# AEGIS_Junction_Box_driver.net
KiCad netlist of a schematic drawn in Altium Designer
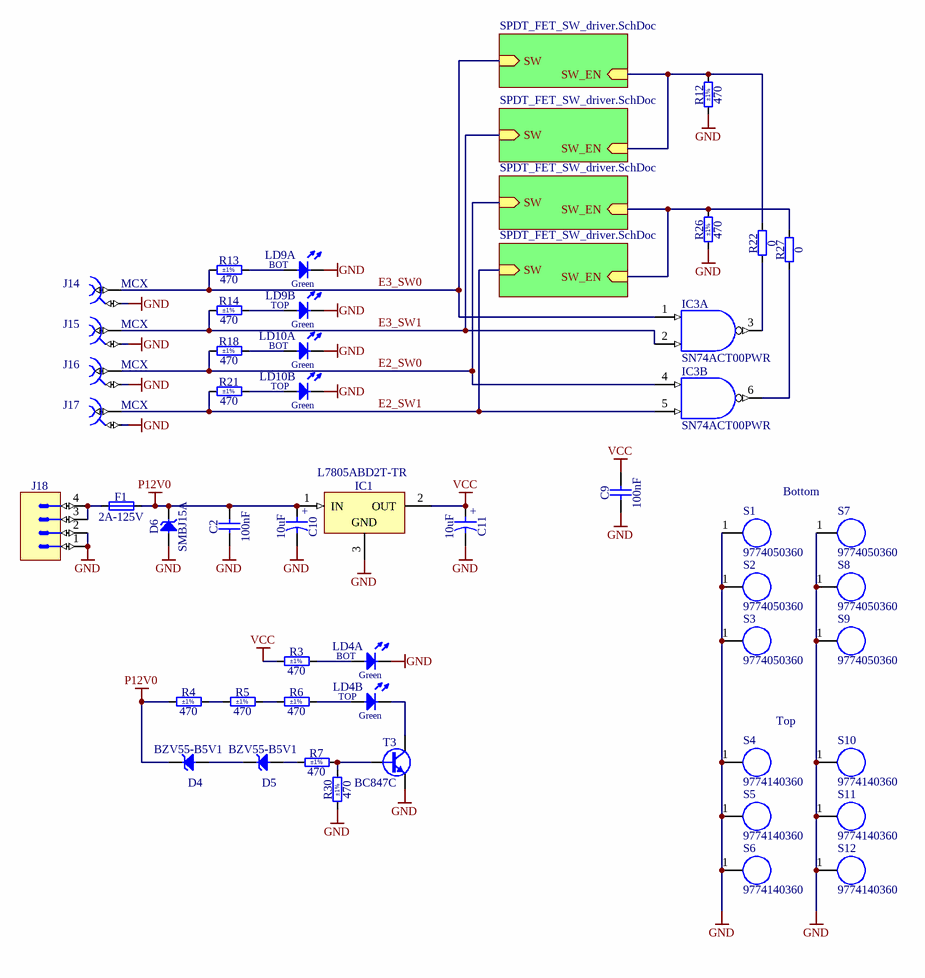
[diagram p0: AEGIS_Junction_Box_driver.SchDoc]

(export (version "E")
  (design (tool "Eeschema 10.0.6"))
  (components
    (comp (ref "C2")
      (value "100nF")
      (footprint "CAPC1005X55N")
      (description "Non-polarised capacitor")
      (fields
        (field (name "PART NUMBER") "CC0402_100NF_16V_10%_X7R")
        (field (name "VOLTAGE") "16V")
        (field (name "AUTHOR") "CERN DEM JLC")
      )
      (libsource (lib "Capacitors") (part "Capacitor - non polarized"))
    )
    (comp (ref "C9")
      (value "100nF")
      (footprint "CAPC1005X55N")
      (description "Non-polarised capacitor")
      (fields
        (field (name "PART NUMBER") "CC0402_100NF_16V_10%_X7R")
        (field (name "VOLTAGE") "16V")
        (field (name "AUTHOR") "CERN DEM JLC")
      )
      (libsource (lib "Capacitors") (part "Capacitor - non polarized"))
    )
    (comp (ref "C10")
      (value "10uF")
      (footprint "CAPMP3216X180N")
      (description "Polarised capacitor")
      (fields
        (field (name "PART NUMBER") "CTE3216-18_10UF_16V_20%_AVX_TCJ")
        (field (name "VOLTAGE") "16V")
        (field (name "AUTHOR") "CERN DEM JLC")
      )
      (libsource (lib "Capacitors") (part "Capacitor - polarized"))
    )
    (comp (ref "C11")
      (value "10uF")
      (footprint "CAPMP3216X180N")
      (description "Polarised capacitor")
      (fields
        (field (name "PART NUMBER") "CTE3216-18_10UF_16V_20%_AVX_TCJ")
        (field (name "VOLTAGE") "16V")
        (field (name "AUTHOR") "CERN DEM JLC")
      )
      (libsource (lib "Capacitors") (part "Capacitor - polarized"))
    )
    (comp (ref "D4")
      (value "BZV55-B5V1")
      (footprint "DIOMELF3515N")
      (description "Zener Diode")
      (fields
        (field (name "VOLTAGE") "5V1")
        (field (name "POWER") "500mW")
        (field (name "AUTHOR") "CERN DEM JLC")
      )
      (libsource (lib "ICs And Semiconductors") (part "Diode Zener"))
    )
    (comp (ref "D5")
      (value "BZV55-B5V1")
      (footprint "DIOMELF3515N")
      (description "Zener Diode")
      (fields
        (field (name "VOLTAGE") "5V1")
        (field (name "POWER") "500mW")
        (field (name "AUTHOR") "CERN DEM JLC")
      )
      (libsource (lib "ICs And Semiconductors") (part "Diode Zener"))
    )
    (comp (ref "D6")
      (value "SMBJ15A")
      (footprint "DIOM5336X265N")
      (description "Zener Diode")
      (fields
        (field (name "VOLTAGE") "15V")
        (field (name "POWER") "600W")
        (field (name "AUTHOR") "CERN DEM JLC")
      )
      (libsource (lib "ICs And Semiconductors") (part "Diode Zener"))
    )
    (comp (ref "F1")
      (value "2A-125V")
      (footprint "FUSE_LITTELFUSE_0154")
      (description "Fuse")
      (fields
        (field (name "PART NUMBER") "FUSE_LITTELFUSE_0154002.DRT")
        (field (name "MANUFACTURER") "LITTELFUSE")
        (field (name "AUTHOR") "CERN DEM JLC")
      )
      (libsource (lib "Eletro-mechanical") (part "Fuse"))
    )
    (comp (ref "IC1")
      (value "L7805ABD2T-TR")
      (footprint "TO254P1542X460-3N-R790X1040")
      (description "3-Terminal Regulator 1=IN 2=OUT 3=GND")
      (fields (field (name "MANUFACTURER") "ST MICROELECTRONICS") (field (name "AUTHOR") "CERN DEM JLC"))
      (libsource (lib "ICs And Semiconductors") (part "REG3 1IN-2OUT-3GND"))
    )
    (comp (ref "IC3")
      (value "SN74ACT00PWR")
      (footprint "SOP65P640X120-14N")
      (description "Quad 2-Input NAND Gate")
      (fields (field (name "MANUFACTURER") "TEXAS INSTRUMENTS") (field (name "AUTHOR") "CERN DEM JLC"))
      (libsource (lib "ICs And Semiconductors") (part "7400"))
    )
    (comp (ref "J14")
      (value "MCX")
      (footprint "AMPHENOL_919-383J-51A")
      (fields
        (field (name "PART NUMBER") "AMPHENOL_919-383J-51A")
        (field (name "MANUFACTURER") "AMPHENOL")
        (field (name "MANUFACTURER PART NUMBER") "919-383J-51A")
        (field (name "AUTHOR") "CERN DEM BC")
      )
      (libsource (lib "Connectors") (part "Coax_1Female_1Shield"))
    )
    (comp (ref "J15")
      (value "MCX")
      (footprint "AMPHENOL_919-383J-51A")
      (fields
        (field (name "PART NUMBER") "AMPHENOL_919-383J-51A")
        (field (name "MANUFACTURER") "AMPHENOL")
        (field (name "MANUFACTURER PART NUMBER") "919-383J-51A")
        (field (name "AUTHOR") "CERN DEM BC")
      )
      (libsource (lib "Connectors") (part "Coax_1Female_1Shield"))
    )
    (comp (ref "J16")
      (value "MCX")
      (footprint "AMPHENOL_919-383J-51A")
      (fields
        (field (name "PART NUMBER") "AMPHENOL_919-383J-51A")
        (field (name "MANUFACTURER") "AMPHENOL")
        (field (name "MANUFACTURER PART NUMBER") "919-383J-51A")
        (field (name "AUTHOR") "CERN DEM BC")
      )
      (libsource (lib "Connectors") (part "Coax_1Female_1Shield"))
    )
    (comp (ref "J17")
      (value "MCX")
      (footprint "AMPHENOL_919-383J-51A")
      (fields
        (field (name "PART NUMBER") "AMPHENOL_919-383J-51A")
        (field (name "MANUFACTURER") "AMPHENOL")
        (field (name "MANUFACTURER PART NUMBER") "919-383J-51A")
        (field (name "AUTHOR") "CERN DEM BC")
      )
      (libsource (lib "Connectors") (part "Coax_1Female_1Shield"))
    )
    (comp (ref "J18")
      (value "Mini-Fit Jr.™")
      (footprint "MOLEX_39-30-0040")
      (description "Connector 4 Male")
      (fields
        (field (name "PART NUMBER") "MOLEX_39-30-0040")
        (field (name "MANUFACTURER") "MOLEX")
        (field (name "AUTHOR") "CERN DEM JLC")
      )
      (libsource (lib "Connectors") (part "Connector 4 Male"))
    )
    (comp (ref "LD4")
      (value "Green")
      (footprint "LED_DIALIGHT_553-0222-210F")
      (description "LED x2 Green 1A2C-BOT_3A4C-TOP")
      (fields
        (field (name "PART NUMBER") "LED_DIALIGHT_553-0222-210F")
        (field (name "MANUFACTURER") "DIALIGHT")
        (field (name "AUTHOR") "CERN DEM BC")
      )
      (libsource (lib "ICs And Semiconductors") (part "LED x2 Green 1A2C-BOT_3A4C-TOP"))
    )
    (comp (ref "LD9")
      (value "Green")
      (footprint "LED_DIALIGHT_553-0222-210F")
      (description "LED x2 Green 1A2C-BOT_3A4C-TOP")
      (fields
        (field (name "PART NUMBER") "LED_DIALIGHT_553-0222-210F")
        (field (name "MANUFACTURER") "DIALIGHT")
        (field (name "AUTHOR") "CERN DEM BC")
      )
      (libsource (lib "ICs And Semiconductors") (part "LED x2 Green 1A2C-BOT_3A4C-TOP"))
    )
    (comp (ref "LD10")
      (value "Green")
      (footprint "LED_DIALIGHT_553-0222-210F")
      (description "LED x2 Green 1A2C-BOT_3A4C-TOP")
      (fields
        (field (name "PART NUMBER") "LED_DIALIGHT_553-0222-210F")
        (field (name "MANUFACTURER") "DIALIGHT")
        (field (name "AUTHOR") "CERN DEM BC")
      )
      (libsource (lib "ICs And Semiconductors") (part "LED x2 Green 1A2C-BOT_3A4C-TOP"))
    )
    (comp (ref "R3")
      (value "470")
      (footprint "RESC1608X55N")
      (description "Resistor - 1%")
      (fields
        (field (name "TOLERANCE") "±1%")
        (field (name "PART NUMBER") "R0603_470R_1%_0.1W_100PPM")
        (field (name "POWER") "0.1W")
        (field (name "AUTHOR") "CERN DEM JLC")
      )
      (libsource (lib "Resistors") (part "Resistor - 1%"))
    )
    (comp (ref "R4")
      (value "470")
      (footprint "RESC1608X55N")
      (description "Resistor - 1%")
      (fields
        (field (name "TOLERANCE") "±1%")
        (field (name "PART NUMBER") "R0603_470R_1%_0.1W_100PPM")
        (field (name "POWER") "0.1W")
        (field (name "AUTHOR") "CERN DEM JLC")
      )
      (libsource (lib "Resistors") (part "Resistor - 1%"))
    )
    (comp (ref "R5")
      (value "470")
      (footprint "RESC1608X55N")
      (description "Resistor - 1%")
      (fields
        (field (name "TOLERANCE") "±1%")
        (field (name "PART NUMBER") "R0603_470R_1%_0.1W_100PPM")
        (field (name "POWER") "0.1W")
        (field (name "AUTHOR") "CERN DEM JLC")
      )
      (libsource (lib "Resistors") (part "Resistor - 1%"))
    )
    (comp (ref "R6")
      (value "470")
      (footprint "RESC1608X55N")
      (description "Resistor - 1%")
      (fields
        (field (name "TOLERANCE") "±1%")
        (field (name "PART NUMBER") "R0603_470R_1%_0.1W_100PPM")
        (field (name "POWER") "0.1W")
        (field (name "AUTHOR") "CERN DEM JLC")
      )
      (libsource (lib "Resistors") (part "Resistor - 1%"))
    )
    (comp (ref "R7")
      (value "470")
      (footprint "RESC1608X55N")
      (description "Resistor - 1%")
      (fields
        (field (name "TOLERANCE") "±1%")
        (field (name "PART NUMBER") "R0603_470R_1%_0.1W_100PPM")
        (field (name "POWER") "0.1W")
        (field (name "AUTHOR") "CERN DEM JLC")
      )
      (libsource (lib "Resistors") (part "Resistor - 1%"))
    )
    (comp (ref "R12")
      (value "470")
      (footprint "RESC1608X55N")
      (description "Resistor - 1%")
      (fields
        (field (name "TOLERANCE") "±1%")
        (field (name "PART NUMBER") "R0603_470R_1%_0.1W_100PPM")
        (field (name "POWER") "0.1W")
        (field (name "AUTHOR") "CERN DEM JLC")
      )
      (libsource (lib "Resistors") (part "Resistor - 1%"))
    )
    (comp (ref "R13")
      (value "470")
      (footprint "RESC1608X55N")
      (description "Resistor - 1%")
      (fields
        (field (name "TOLERANCE") "±1%")
        (field (name "PART NUMBER") "R0603_470R_1%_0.1W_100PPM")
        (field (name "POWER") "0.1W")
        (field (name "AUTHOR") "CERN DEM JLC")
      )
      (libsource (lib "Resistors") (part "Resistor - 1%"))
    )
    (comp (ref "R14")
      (value "470")
      (footprint "RESC1608X55N")
      (description "Resistor - 1%")
      (fields
        (field (name "TOLERANCE") "±1%")
        (field (name "PART NUMBER") "R0603_470R_1%_0.1W_100PPM")
        (field (name "POWER") "0.1W")
        (field (name "AUTHOR") "CERN DEM JLC")
      )
      (libsource (lib "Resistors") (part "Resistor - 1%"))
    )
    (comp (ref "R18")
      (value "470")
      (footprint "RESC1608X55N")
      (description "Resistor - 1%")
      (fields
        (field (name "TOLERANCE") "±1%")
        (field (name "PART NUMBER") "R0603_470R_1%_0.1W_100PPM")
        (field (name "POWER") "0.1W")
        (field (name "AUTHOR") "CERN DEM JLC")
      )
      (libsource (lib "Resistors") (part "Resistor - 1%"))
    )
    (comp (ref "R21")
      (value "470")
      (footprint "RESC1608X55N")
      (description "Resistor - 1%")
      (fields
        (field (name "TOLERANCE") "±1%")
        (field (name "PART NUMBER") "R0603_470R_1%_0.1W_100PPM")
        (field (name "POWER") "0.1W")
        (field (name "AUTHOR") "CERN DEM JLC")
      )
      (libsource (lib "Resistors") (part "Resistor - 1%"))
    )
    (comp (ref "R22")
      (value "0")
      (footprint "RESC1608X55N")
      (description "Resistor")
      (fields
        (field (name "PART NUMBER") "R0603_0R_JUMPER")
        (field (name "MANUFACTURER") "GENERIC")
        (field (name "AUTHOR") "CERN DEM JLC")
      )
      (libsource (lib "Resistors") (part "Resistor"))
    )
    (comp (ref "R26")
      (value "470")
      (footprint "RESC1608X55N")
      (description "Resistor - 1%")
      (fields
        (field (name "TOLERANCE") "±1%")
        (field (name "PART NUMBER") "R0603_470R_1%_0.1W_100PPM")
        (field (name "POWER") "0.1W")
        (field (name "AUTHOR") "CERN DEM JLC")
      )
      (libsource (lib "Resistors") (part "Resistor - 1%"))
    )
    (comp (ref "R27")
      (value "0")
      (footprint "RESC1608X55N")
      (description "Resistor")
      (fields
        (field (name "PART NUMBER") "R0603_0R_JUMPER")
        (field (name "MANUFACTURER") "GENERIC")
        (field (name "AUTHOR") "CERN DEM JLC")
      )
      (libsource (lib "Resistors") (part "Resistor"))
    )
    (comp (ref "R30")
      (value "470")
      (footprint "RESC1608X55N")
      (description "Resistor - 1%")
      (fields
        (field (name "TOLERANCE") "±1%")
        (field (name "PART NUMBER") "R0603_470R_1%_0.1W_100PPM")
        (field (name "POWER") "0.1W")
        (field (name "AUTHOR") "CERN DEM JLC")
      )
      (libsource (lib "Resistors") (part "Resistor - 1%"))
    )
    (comp (ref "S1")
      (value "9774050360")
      (footprint "9774050360")
      (description "WA-SMSI SMD Steel Spacer with internal Thread")
      (fields (field (name "MANUFACTURER") "Wurth Elektronik") (field (name "CREATED BY") "Baojun Chen"))
      (libsource (lib "Altium_SMSI_SMT_STEEL_SPACER_M2_5_THREAD_INTERNAL_rev15a") (part "WA-SMSI,  9774050360"))
    )
    (comp (ref "S2")
      (value "9774050360")
      (footprint "9774050360")
      (description "WA-SMSI SMD Steel Spacer with internal Thread")
      (fields (field (name "MANUFACTURER") "Wurth Elektronik") (field (name "CREATED BY") "Baojun Chen"))
      (libsource (lib "Altium_SMSI_SMT_STEEL_SPACER_M2_5_THREAD_INTERNAL_rev15a") (part "WA-SMSI,  9774050360"))
    )
    (comp (ref "S3")
      (value "9774050360")
      (footprint "9774050360")
      (description "WA-SMSI SMD Steel Spacer with internal Thread")
      (fields (field (name "MANUFACTURER") "Wurth Elektronik") (field (name "CREATED BY") "Baojun Chen"))
      (libsource (lib "Altium_SMSI_SMT_STEEL_SPACER_M2_5_THREAD_INTERNAL_rev15a") (part "WA-SMSI,  9774050360"))
    )
    (comp (ref "S4")
      (value "9774140360")
      (footprint "9774140360")
      (description "WA-SMSI SMD Steel Spacer with internal Thread")
      (fields (field (name "MANUFACTURER") "Wurth Elektronik") (field (name "CREATED BY") "Baojun Chen"))
      (libsource (lib "Altium_SMSI_SMT_STEEL_SPACER_M2_5_THREAD_INTERNAL_rev15a") (part "WA-SMSI,  9774140360"))
    )
    (comp (ref "S5")
      (value "9774140360")
      (footprint "9774140360")
      (description "WA-SMSI SMD Steel Spacer with internal Thread")
      (fields (field (name "MANUFACTURER") "Wurth Elektronik") (field (name "CREATED BY") "Baojun Chen"))
      (libsource (lib "Altium_SMSI_SMT_STEEL_SPACER_M2_5_THREAD_INTERNAL_rev15a") (part "WA-SMSI,  9774140360"))
    )
    (comp (ref "S6")
      (value "9774140360")
      (footprint "9774140360")
      (description "WA-SMSI SMD Steel Spacer with internal Thread")
      (fields (field (name "MANUFACTURER") "Wurth Elektronik") (field (name "CREATED BY") "Baojun Chen"))
      (libsource (lib "Altium_SMSI_SMT_STEEL_SPACER_M2_5_THREAD_INTERNAL_rev15a") (part "WA-SMSI,  9774140360"))
    )
    (comp (ref "S7")
      (value "9774050360")
      (footprint "9774050360")
      (description "WA-SMSI SMD Steel Spacer with internal Thread")
      (fields (field (name "MANUFACTURER") "Wurth Elektronik") (field (name "CREATED BY") "Baojun Chen"))
      (libsource (lib "Altium_SMSI_SMT_STEEL_SPACER_M2_5_THREAD_INTERNAL_rev15a") (part "WA-SMSI,  9774050360"))
    )
    (comp (ref "S8")
      (value "9774050360")
      (footprint "9774050360")
      (description "WA-SMSI SMD Steel Spacer with internal Thread")
      (fields (field (name "MANUFACTURER") "Wurth Elektronik") (field (name "CREATED BY") "Baojun Chen"))
      (libsource (lib "Altium_SMSI_SMT_STEEL_SPACER_M2_5_THREAD_INTERNAL_rev15a") (part "WA-SMSI,  9774050360"))
    )
    (comp (ref "S9")
      (value "9774050360")
      (footprint "9774050360")
      (description "WA-SMSI SMD Steel Spacer with internal Thread")
      (fields (field (name "MANUFACTURER") "Wurth Elektronik") (field (name "CREATED BY") "Baojun Chen"))
      (libsource (lib "Altium_SMSI_SMT_STEEL_SPACER_M2_5_THREAD_INTERNAL_rev15a") (part "WA-SMSI,  9774050360"))
    )
    (comp (ref "S10")
      (value "9774140360")
      (footprint "9774140360")
      (description "WA-SMSI SMD Steel Spacer with internal Thread")
      (fields (field (name "MANUFACTURER") "Wurth Elektronik") (field (name "CREATED BY") "Baojun Chen"))
      (libsource (lib "Altium_SMSI_SMT_STEEL_SPACER_M2_5_THREAD_INTERNAL_rev15a") (part "WA-SMSI,  9774140360"))
    )
    (comp (ref "S11")
      (value "9774140360")
      (footprint "9774140360")
      (description "WA-SMSI SMD Steel Spacer with internal Thread")
      (fields (field (name "MANUFACTURER") "Wurth Elektronik") (field (name "CREATED BY") "Baojun Chen"))
      (libsource (lib "Altium_SMSI_SMT_STEEL_SPACER_M2_5_THREAD_INTERNAL_rev15a") (part "WA-SMSI,  9774140360"))
    )
    (comp (ref "S12")
      (value "9774140360")
      (footprint "9774140360")
      (description "WA-SMSI SMD Steel Spacer with internal Thread")
      (fields (field (name "MANUFACTURER") "Wurth Elektronik") (field (name "CREATED BY") "Baojun Chen"))
      (libsource (lib "Altium_SMSI_SMT_STEEL_SPACER_M2_5_THREAD_INTERNAL_rev15a") (part "WA-SMSI,  9774140360"))
    )
    (comp (ref "T3")
      (value "BC847C")
      (footprint "SOT95P240X110-3N")
      (description "NPN Transistor")
      (fields (field (name "MANUFACTURER") "INFINEON") (field (name "AUTHOR") "CERN DEM JLC"))
      (libsource (lib "ICs And Semiconductors") (part "NPN B1 E2 C3"))
    )
  )
  (nets
    (net (code "1") (name "/E2_SW0") (class "Default")
      (node (ref "IC3") (pin "4") (pinfunction "A_4") (pintype "input"))
      (node (ref "J16") (pin "1") (pinfunction "1_1") (pintype "bidirectional"))
      (node (ref "R18") (pin "1") (pinfunction "1_1") (pintype "passive"))
    )
    (net (code "2") (name "/E2_SW1") (class "Default")
      (node (ref "IC3") (pin "5") (pinfunction "B_5") (pintype "input"))
      (node (ref "J17") (pin "1") (pinfunction "1_1") (pintype "bidirectional"))
      (node (ref "R21") (pin "1") (pinfunction "1_1") (pintype "passive"))
    )
    (net (code "3") (name "/E3_SW0") (class "Default")
      (node (ref "IC3") (pin "1") (pinfunction "A_1") (pintype "input"))
      (node (ref "J14") (pin "1") (pinfunction "1_1") (pintype "bidirectional"))
      (node (ref "R13") (pin "1") (pinfunction "1_1") (pintype "passive"))
    )
    (net (code "4") (name "/E3_SW1") (class "Default")
      (node (ref "IC3") (pin "2") (pinfunction "B_2") (pintype "input"))
      (node (ref "J15") (pin "1") (pinfunction "1_1") (pintype "bidirectional"))
      (node (ref "R14") (pin "1") (pinfunction "1_1") (pintype "passive"))
    )
    (net (code "5") (name "/SW_EN") (class "Default")
      (node (ref "R26") (pin "2") (pinfunction "2_2") (pintype "passive"))
      (node (ref "R27") (pin "2") (pinfunction "2_2") (pintype "passive"))
    )
    (net (code "6") (name "/SW_EN_1") (class "Default")
      (node (ref "R12") (pin "2") (pinfunction "2_2") (pintype "passive"))
      (node (ref "R22") (pin "2") (pinfunction "2_2") (pintype "passive"))
    )
    (net (code "7") (name "GND") (class "Default")
      (node (ref "C10") (pin "2") (pinfunction "2_2") (pintype "passive"))
      (node (ref "C11") (pin "2") (pinfunction "2_2") (pintype "passive"))
      (node (ref "C2") (pin "1") (pinfunction "1_1") (pintype "passive"))
      (node (ref "C9") (pin "1") (pinfunction "1_1") (pintype "passive"))
      (node (ref "D6") (pin "2") (pinfunction "A_2") (pintype "passive"))
      (node (ref "IC1") (pin "3") (pinfunction "GND_3") (pintype "power_in"))
      (node (ref "IC3") (pin "7") (pinfunction "GND_7") (pintype "power_in"))
      (node (ref "J14") (pin "2") (pinfunction "2_2") (pintype "bidirectional"))
      (node (ref "J15") (pin "2") (pinfunction "2_2") (pintype "bidirectional"))
      (node (ref "J16") (pin "2") (pinfunction "2_2") (pintype "bidirectional"))
      (node (ref "J17") (pin "2") (pinfunction "2_2") (pintype "bidirectional"))
      (node (ref "J18") (pin "1") (pinfunction "1_1") (pintype "bidirectional"))
      (node (ref "J18") (pin "2") (pinfunction "2_2") (pintype "bidirectional"))
      (node (ref "LD10") (pin "2") (pinfunction "C_2") (pintype "passive"))
      (node (ref "LD10") (pin "4") (pinfunction "C_4") (pintype "passive"))
      (node (ref "LD4") (pin "2") (pinfunction "C_2") (pintype "passive"))
      (node (ref "LD9") (pin "2") (pinfunction "C_2") (pintype "passive"))
      (node (ref "LD9") (pin "4") (pinfunction "C_4") (pintype "passive"))
      (node (ref "R12") (pin "1") (pinfunction "1_1") (pintype "passive"))
      (node (ref "R26") (pin "1") (pinfunction "1_1") (pintype "passive"))
      (node (ref "R30") (pin "1") (pinfunction "1_1") (pintype "passive"))
      (node (ref "S1") (pin "1") (pinfunction "1_1") (pintype "passive"))
      (node (ref "S10") (pin "1") (pinfunction "1_1") (pintype "passive"))
      (node (ref "S11") (pin "1") (pinfunction "1_1") (pintype "passive"))
      (node (ref "S12") (pin "1") (pinfunction "1_1") (pintype "passive"))
      (node (ref "S2") (pin "1") (pinfunction "1_1") (pintype "passive"))
      (node (ref "S3") (pin "1") (pinfunction "1_1") (pintype "passive"))
      (node (ref "S4") (pin "1") (pinfunction "1_1") (pintype "passive"))
      (node (ref "S5") (pin "1") (pinfunction "1_1") (pintype "passive"))
      (node (ref "S6") (pin "1") (pinfunction "1_1") (pintype "passive"))
      (node (ref "S7") (pin "1") (pinfunction "1_1") (pintype "passive"))
      (node (ref "S8") (pin "1") (pinfunction "1_1") (pintype "passive"))
      (node (ref "S9") (pin "1") (pinfunction "1_1") (pintype "passive"))
      (node (ref "T3") (pin "2") (pinfunction "E_2") (pintype "passive"))
    )
    (net (code "8") (name "Net-(D4-A)") (class "Default")
      (node (ref "D4") (pin "2") (pinfunction "A_2") (pintype "passive"))
      (node (ref "D5") (pin "1") (pinfunction "C_1") (pintype "passive"))
    )
    (net (code "9") (name "Net-(D5-A)") (class "Default")
      (node (ref "D5") (pin "2") (pinfunction "A_2") (pintype "passive"))
      (node (ref "R7") (pin "1") (pinfunction "1_1") (pintype "passive"))
    )
    (net (code "10") (name "Net-(F1-Pad1)") (class "Default")
      (node (ref "F1") (pin "1") (pinfunction "1_1") (pintype "passive"))
      (node (ref "J18") (pin "3") (pinfunction "3_3") (pintype "bidirectional"))
      (node (ref "J18") (pin "4") (pinfunction "4_4") (pintype "bidirectional"))
    )
    (net (code "11") (name "Net-(IC3A-~{O})") (class "Default")
      (node (ref "IC3") (pin "3") (pinfunction "~{O}_3") (pintype "output"))
      (node (ref "R22") (pin "1") (pinfunction "1_1") (pintype "passive"))
    )
    (net (code "12") (name "Net-(IC3B-~{O})") (class "Default")
      (node (ref "IC3") (pin "6") (pinfunction "~{O}_6") (pintype "output"))
      (node (ref "R27") (pin "1") (pinfunction "1_1") (pintype "passive"))
    )
    (net (code "13") (name "Net-(LD4A-A)") (class "Default")
      (node (ref "LD4") (pin "1") (pinfunction "A_1") (pintype "passive"))
      (node (ref "R3") (pin "2") (pinfunction "2_2") (pintype "passive"))
    )
    (net (code "14") (name "Net-(LD4B-A)") (class "Default")
      (node (ref "LD4") (pin "3") (pinfunction "A_3") (pintype "passive"))
      (node (ref "R6") (pin "2") (pinfunction "2_2") (pintype "passive"))
    )
    (net (code "15") (name "Net-(LD4B-C)") (class "Default")
      (node (ref "LD4") (pin "4") (pinfunction "C_4") (pintype "passive"))
      (node (ref "T3") (pin "3") (pinfunction "C_3") (pintype "passive"))
    )
    (net (code "16") (name "Net-(LD9A-A)") (class "Default")
      (node (ref "LD9") (pin "1") (pinfunction "A_1") (pintype "passive"))
      (node (ref "R13") (pin "2") (pinfunction "2_2") (pintype "passive"))
    )
    (net (code "17") (name "Net-(LD9B-A)") (class "Default")
      (node (ref "LD9") (pin "3") (pinfunction "A_3") (pintype "passive"))
      (node (ref "R14") (pin "2") (pinfunction "2_2") (pintype "passive"))
    )
    (net (code "18") (name "Net-(LD10A-A)") (class "Default")
      (node (ref "LD10") (pin "1") (pinfunction "A_1") (pintype "passive"))
      (node (ref "R18") (pin "2") (pinfunction "2_2") (pintype "passive"))
    )
    (net (code "19") (name "Net-(LD10B-A)") (class "Default")
      (node (ref "LD10") (pin "3") (pinfunction "A_3") (pintype "passive"))
      (node (ref "R21") (pin "2") (pinfunction "2_2") (pintype "passive"))
    )
    (net (code "20") (name "Net-(R4-Pad2)") (class "Default")
      (node (ref "R4") (pin "2") (pinfunction "2_2") (pintype "passive"))
      (node (ref "R5") (pin "1") (pinfunction "1_1") (pintype "passive"))
    )
    (net (code "21") (name "Net-(R5-Pad2)") (class "Default")
      (node (ref "R5") (pin "2") (pinfunction "2_2") (pintype "passive"))
      (node (ref "R6") (pin "1") (pinfunction "1_1") (pintype "passive"))
    )
    (net (code "22") (name "Net-(T3-B)") (class "Default")
      (node (ref "R30") (pin "2") (pinfunction "2_2") (pintype "passive"))
      (node (ref "R7") (pin "2") (pinfunction "2_2") (pintype "passive"))
      (node (ref "T3") (pin "1") (pinfunction "B_1") (pintype "passive"))
    )
    (net (code "23") (name "P12V0") (class "Default")
      (node (ref "C10") (pin "1") (pinfunction "1_1") (pintype "passive"))
      (node (ref "C2") (pin "2") (pinfunction "2_2") (pintype "passive"))
      (node (ref "D4") (pin "1") (pinfunction "C_1") (pintype "passive"))
      (node (ref "D6") (pin "1") (pinfunction "C_1") (pintype "passive"))
      (node (ref "F1") (pin "2") (pinfunction "2_2") (pintype "passive"))
      (node (ref "IC1") (pin "1") (pinfunction "IN_1") (pintype "input"))
      (node (ref "R4") (pin "1") (pinfunction "1_1") (pintype "passive"))
    )
    (net (code "24") (name "VCC") (class "Default")
      (node (ref "C11") (pin "1") (pinfunction "1_1") (pintype "passive"))
      (node (ref "C9") (pin "2") (pinfunction "2_2") (pintype "passive"))
      (node (ref "IC1") (pin "2") (pinfunction "OUT_2") (pintype "power_in"))
      (node (ref "IC3") (pin "14") (pinfunction "VCC_14") (pintype "power_in"))
      (node (ref "R3") (pin "1") (pinfunction "1_1") (pintype "passive"))
    )
  )
)
